# Bus_V3_0.net
KiCad netlist of a schematic drawn in EAGLE
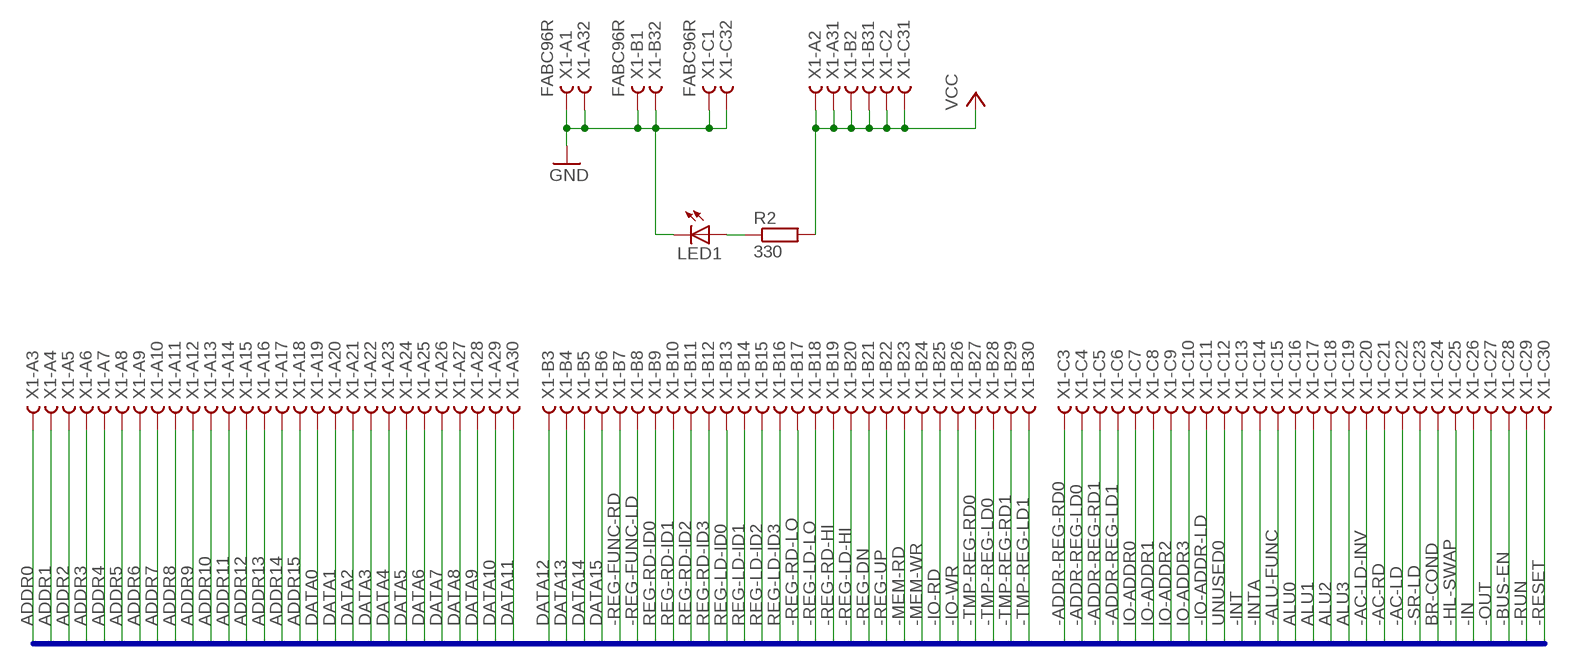
[diagram p0: schematic, sheet 1]

(export (version "E")
  (design (tool "Eeschema 10.0.6"))
  (components
    (comp (ref "LED1")
      (value "LED5MM")
      (footprint "eagle-import:LED5MM")
      (libsource (lib "eagle-import") (part "LED5MM"))
    )
    (comp (ref "R2")
      (value "330")
      (footprint "eagle-import:0207_10")
      (libsource (lib "eagle-import") (part "R0207/10"))
    )
    (comp (ref "X1")
      (value "FABC96R")
      (footprint "eagle-import:FABC96R")
      (libsource (lib "eagle-import") (part "FABC96R"))
    )
  )
  (nets
    (net (code "1") (name "/-AC-LD") (class "Default")
      (node (ref "X1") (pin "C22") (pinfunction "B_C22") (pintype "passive"))
    )
    (net (code "2") (name "/-AC-LD-INV") (class "Default")
      (node (ref "X1") (pin "C20") (pinfunction "B_C20") (pintype "passive"))
    )
    (net (code "3") (name "/-AC-RD") (class "Default")
      (node (ref "X1") (pin "C21") (pinfunction "B_C21") (pintype "passive"))
    )
    (net (code "4") (name "/-ADDR-REG-LD0") (class "Default")
      (node (ref "X1") (pin "C4") (pinfunction "B_C4") (pintype "passive"))
    )
    (net (code "5") (name "/-ADDR-REG-LD1") (class "Default")
      (node (ref "X1") (pin "C6") (pinfunction "B_C6") (pintype "passive"))
    )
    (net (code "6") (name "/-ADDR-REG-RD0") (class "Default")
      (node (ref "X1") (pin "C3") (pinfunction "B_C3") (pintype "passive"))
    )
    (net (code "7") (name "/-ADDR-REG-RD1") (class "Default")
      (node (ref "X1") (pin "C5") (pinfunction "B_C5") (pintype "passive"))
    )
    (net (code "8") (name "/-ALU-FUNC") (class "Default")
      (node (ref "X1") (pin "C15") (pinfunction "B_C15") (pintype "passive"))
    )
    (net (code "9") (name "/-BUS-EN") (class "Default")
      (node (ref "X1") (pin "C28") (pinfunction "B_C28") (pintype "passive"))
    )
    (net (code "10") (name "/-HL-SWAP") (class "Default")
      (node (ref "X1") (pin "C25") (pinfunction "B_C25") (pintype "passive"))
    )
    (net (code "11") (name "/-IN") (class "Default")
      (node (ref "X1") (pin "C26") (pinfunction "B_C26") (pintype "passive"))
    )
    (net (code "12") (name "/-INT") (class "Default")
      (node (ref "X1") (pin "C13") (pinfunction "B_C13") (pintype "passive"))
    )
    (net (code "13") (name "/-INTA") (class "Default")
      (node (ref "X1") (pin "C14") (pinfunction "B_C14") (pintype "passive"))
    )
    (net (code "14") (name "/-IO-ADDR-LD") (class "Default")
      (node (ref "X1") (pin "C11") (pinfunction "B_C11") (pintype "passive"))
    )
    (net (code "15") (name "/-IO-RD") (class "Default")
      (node (ref "X1") (pin "B25") (pinfunction "B_B25") (pintype "passive"))
    )
    (net (code "16") (name "/-IO-WR") (class "Default")
      (node (ref "X1") (pin "B26") (pinfunction "B_B26") (pintype "passive"))
    )
    (net (code "17") (name "/-MEM-RD") (class "Default")
      (node (ref "X1") (pin "B23") (pinfunction "B_B23") (pintype "passive"))
    )
    (net (code "18") (name "/-MEM-WR") (class "Default")
      (node (ref "X1") (pin "B24") (pinfunction "B_B24") (pintype "passive"))
    )
    (net (code "19") (name "/-OUT") (class "Default")
      (node (ref "X1") (pin "C27") (pinfunction "B_C27") (pintype "passive"))
    )
    (net (code "20") (name "/-REG-DN") (class "Default")
      (node (ref "X1") (pin "B21") (pinfunction "B_B21") (pintype "passive"))
    )
    (net (code "21") (name "/-REG-FUNC-LD") (class "Default")
      (node (ref "X1") (pin "B8") (pinfunction "B_B8") (pintype "passive"))
    )
    (net (code "22") (name "/-REG-FUNC-RD") (class "Default")
      (node (ref "X1") (pin "B7") (pinfunction "B_B7") (pintype "passive"))
    )
    (net (code "23") (name "/-REG-LD-HI") (class "Default")
      (node (ref "X1") (pin "B20") (pinfunction "B_B20") (pintype "passive"))
    )
    (net (code "24") (name "/-REG-LD-LO") (class "Default")
      (node (ref "X1") (pin "B18") (pinfunction "B_B18") (pintype "passive"))
    )
    (net (code "25") (name "/-REG-RD-HI") (class "Default")
      (node (ref "X1") (pin "B19") (pinfunction "B_B19") (pintype "passive"))
    )
    (net (code "26") (name "/-REG-RD-LO") (class "Default")
      (node (ref "X1") (pin "B17") (pinfunction "B_B17") (pintype "passive"))
    )
    (net (code "27") (name "/-REG-UP") (class "Default")
      (node (ref "X1") (pin "B22") (pinfunction "B_B22") (pintype "passive"))
    )
    (net (code "28") (name "/-RESET") (class "Default")
      (node (ref "X1") (pin "C30") (pinfunction "B_C30") (pintype "passive"))
    )
    (net (code "29") (name "/-RUN") (class "Default")
      (node (ref "X1") (pin "C29") (pinfunction "B_C29") (pintype "passive"))
    )
    (net (code "30") (name "/-SR-LD") (class "Default")
      (node (ref "X1") (pin "C23") (pinfunction "B_C23") (pintype "passive"))
    )
    (net (code "31") (name "/-TMP-REG-LD0") (class "Default")
      (node (ref "X1") (pin "B28") (pinfunction "B_B28") (pintype "passive"))
    )
    (net (code "32") (name "/-TMP-REG-LD1") (class "Default")
      (node (ref "X1") (pin "B30") (pinfunction "B_B30") (pintype "passive"))
    )
    (net (code "33") (name "/-TMP-REG-RD0") (class "Default")
      (node (ref "X1") (pin "B27") (pinfunction "B_B27") (pintype "passive"))
    )
    (net (code "34") (name "/-TMP-REG-RD1") (class "Default")
      (node (ref "X1") (pin "B29") (pinfunction "B_B29") (pintype "passive"))
    )
    (net (code "35") (name "/ADDR0") (class "Default")
      (node (ref "X1") (pin "A3") (pinfunction "B_A3") (pintype "passive"))
    )
    (net (code "36") (name "/ADDR1") (class "Default")
      (node (ref "X1") (pin "A4") (pinfunction "B_A4") (pintype "passive"))
    )
    (net (code "37") (name "/ADDR2") (class "Default")
      (node (ref "X1") (pin "A5") (pinfunction "B_A5") (pintype "passive"))
    )
    (net (code "38") (name "/ADDR3") (class "Default")
      (node (ref "X1") (pin "A6") (pinfunction "B_A6") (pintype "passive"))
    )
    (net (code "39") (name "/ADDR4") (class "Default")
      (node (ref "X1") (pin "A7") (pinfunction "B_A7") (pintype "passive"))
    )
    (net (code "40") (name "/ADDR5") (class "Default")
      (node (ref "X1") (pin "A8") (pinfunction "B_A8") (pintype "passive"))
    )
    (net (code "41") (name "/ADDR6") (class "Default")
      (node (ref "X1") (pin "A9") (pinfunction "B_A9") (pintype "passive"))
    )
    (net (code "42") (name "/ADDR7") (class "Default")
      (node (ref "X1") (pin "A10") (pinfunction "B_A10") (pintype "passive"))
    )
    (net (code "43") (name "/ADDR8") (class "Default")
      (node (ref "X1") (pin "A11") (pinfunction "B_A11") (pintype "passive"))
    )
    (net (code "44") (name "/ADDR9") (class "Default")
      (node (ref "X1") (pin "A12") (pinfunction "B_A12") (pintype "passive"))
    )
    (net (code "45") (name "/ADDR10") (class "Default")
      (node (ref "X1") (pin "A13") (pinfunction "B_A13") (pintype "passive"))
    )
    (net (code "46") (name "/ADDR11") (class "Default")
      (node (ref "X1") (pin "A14") (pinfunction "B_A14") (pintype "passive"))
    )
    (net (code "47") (name "/ADDR12") (class "Default")
      (node (ref "X1") (pin "A15") (pinfunction "B_A15") (pintype "passive"))
    )
    (net (code "48") (name "/ADDR13") (class "Default")
      (node (ref "X1") (pin "A16") (pinfunction "B_A16") (pintype "passive"))
    )
    (net (code "49") (name "/ADDR14") (class "Default")
      (node (ref "X1") (pin "A17") (pinfunction "B_A17") (pintype "passive"))
    )
    (net (code "50") (name "/ADDR15") (class "Default")
      (node (ref "X1") (pin "A18") (pinfunction "B_A18") (pintype "passive"))
    )
    (net (code "51") (name "/ALU0") (class "Default")
      (node (ref "X1") (pin "C16") (pinfunction "B_C16") (pintype "passive"))
    )
    (net (code "52") (name "/ALU1") (class "Default")
      (node (ref "X1") (pin "C17") (pinfunction "B_C17") (pintype "passive"))
    )
    (net (code "53") (name "/ALU2") (class "Default")
      (node (ref "X1") (pin "C18") (pinfunction "B_C18") (pintype "passive"))
    )
    (net (code "54") (name "/ALU3") (class "Default")
      (node (ref "X1") (pin "C19") (pinfunction "B_C19") (pintype "passive"))
    )
    (net (code "55") (name "/BR-COND") (class "Default")
      (node (ref "X1") (pin "C24") (pinfunction "B_C24") (pintype "passive"))
    )
    (net (code "56") (name "/DATA0") (class "Default")
      (node (ref "X1") (pin "A19") (pinfunction "B_A19") (pintype "passive"))
    )
    (net (code "57") (name "/DATA1") (class "Default")
      (node (ref "X1") (pin "A20") (pinfunction "B_A20") (pintype "passive"))
    )
    (net (code "58") (name "/DATA2") (class "Default")
      (node (ref "X1") (pin "A21") (pinfunction "B_A21") (pintype "passive"))
    )
    (net (code "59") (name "/DATA3") (class "Default")
      (node (ref "X1") (pin "A22") (pinfunction "B_A22") (pintype "passive"))
    )
    (net (code "60") (name "/DATA4") (class "Default")
      (node (ref "X1") (pin "A23") (pinfunction "B_A23") (pintype "passive"))
    )
    (net (code "61") (name "/DATA5") (class "Default")
      (node (ref "X1") (pin "A24") (pinfunction "B_A24") (pintype "passive"))
    )
    (net (code "62") (name "/DATA6") (class "Default")
      (node (ref "X1") (pin "A25") (pinfunction "B_A25") (pintype "passive"))
    )
    (net (code "63") (name "/DATA7") (class "Default")
      (node (ref "X1") (pin "A26") (pinfunction "B_A26") (pintype "passive"))
    )
    (net (code "64") (name "/DATA8") (class "Default")
      (node (ref "X1") (pin "A27") (pinfunction "B_A27") (pintype "passive"))
    )
    (net (code "65") (name "/DATA9") (class "Default")
      (node (ref "X1") (pin "A28") (pinfunction "B_A28") (pintype "passive"))
    )
    (net (code "66") (name "/DATA10") (class "Default")
      (node (ref "X1") (pin "A29") (pinfunction "B_A29") (pintype "passive"))
    )
    (net (code "67") (name "/DATA11") (class "Default")
      (node (ref "X1") (pin "A30") (pinfunction "B_A30") (pintype "passive"))
    )
    (net (code "68") (name "/DATA12") (class "Default")
      (node (ref "X1") (pin "B3") (pinfunction "B_B3") (pintype "passive"))
    )
    (net (code "69") (name "/DATA13") (class "Default")
      (node (ref "X1") (pin "B4") (pinfunction "B_B4") (pintype "passive"))
    )
    (net (code "70") (name "/DATA14") (class "Default")
      (node (ref "X1") (pin "B5") (pinfunction "B_B5") (pintype "passive"))
    )
    (net (code "71") (name "/DATA15") (class "Default")
      (node (ref "X1") (pin "B6") (pinfunction "B_B6") (pintype "passive"))
    )
    (net (code "72") (name "/IO-ADDR0") (class "Default")
      (node (ref "X1") (pin "C7") (pinfunction "B_C7") (pintype "passive"))
    )
    (net (code "73") (name "/IO-ADDR1") (class "Default")
      (node (ref "X1") (pin "C8") (pinfunction "B_C8") (pintype "passive"))
    )
    (net (code "74") (name "/IO-ADDR2") (class "Default")
      (node (ref "X1") (pin "C9") (pinfunction "B_C9") (pintype "passive"))
    )
    (net (code "75") (name "/IO-ADDR3") (class "Default")
      (node (ref "X1") (pin "C10") (pinfunction "B_C10") (pintype "passive"))
    )
    (net (code "76") (name "/REG-LD-ID0") (class "Default")
      (node (ref "X1") (pin "B13") (pinfunction "B_B13") (pintype "passive"))
    )
    (net (code "77") (name "/REG-LD-ID1") (class "Default")
      (node (ref "X1") (pin "B14") (pinfunction "B_B14") (pintype "passive"))
    )
    (net (code "78") (name "/REG-LD-ID2") (class "Default")
      (node (ref "X1") (pin "B15") (pinfunction "B_B15") (pintype "passive"))
    )
    (net (code "79") (name "/REG-LD-ID3") (class "Default")
      (node (ref "X1") (pin "B16") (pinfunction "B_B16") (pintype "passive"))
    )
    (net (code "80") (name "/REG-RD-ID0") (class "Default")
      (node (ref "X1") (pin "B9") (pinfunction "B_B9") (pintype "passive"))
    )
    (net (code "81") (name "/REG-RD-ID1") (class "Default")
      (node (ref "X1") (pin "B10") (pinfunction "B_B10") (pintype "passive"))
    )
    (net (code "82") (name "/REG-RD-ID2") (class "Default")
      (node (ref "X1") (pin "B11") (pinfunction "B_B11") (pintype "passive"))
    )
    (net (code "83") (name "/REG-RD-ID3") (class "Default")
      (node (ref "X1") (pin "B12") (pinfunction "B_B12") (pintype "passive"))
    )
    (net (code "84") (name "/UNUSED0") (class "Default")
      (node (ref "X1") (pin "C12") (pinfunction "B_C12") (pintype "passive"))
    )
    (net (code "85") (name "GND") (class "Default")
      (node (ref "LED1") (pin "K") (pinfunction "C_K") (pintype "passive"))
      (node (ref "X1") (pin "A1") (pinfunction "B_A1") (pintype "passive"))
      (node (ref "X1") (pin "A32") (pinfunction "B_A32") (pintype "passive"))
      (node (ref "X1") (pin "B1") (pinfunction "B_B1") (pintype "passive"))
      (node (ref "X1") (pin "B32") (pinfunction "B_B32") (pintype "passive"))
      (node (ref "X1") (pin "C1") (pinfunction "B_C1") (pintype "passive"))
      (node (ref "X1") (pin "C32") (pinfunction "B_C32") (pintype "passive"))
    )
    (net (code "86") (name "Net-(LED1-PadA)") (class "Default")
      (node (ref "LED1") (pin "A") (pinfunction "A_A") (pintype "passive"))
      (node (ref "R2") (pin "1") (pinfunction "1_1") (pintype "passive"))
    )
    (net (code "87") (name "VCC") (class "Default")
      (node (ref "R2") (pin "2") (pinfunction "2_2") (pintype "passive"))
      (node (ref "X1") (pin "A2") (pinfunction "B_A2") (pintype "passive"))
      (node (ref "X1") (pin "A31") (pinfunction "B_A31") (pintype "passive"))
      (node (ref "X1") (pin "B2") (pinfunction "B_B2") (pintype "passive"))
      (node (ref "X1") (pin "B31") (pinfunction "B_B31") (pintype "passive"))
      (node (ref "X1") (pin "C2") (pinfunction "B_C2") (pintype "passive"))
      (node (ref "X1") (pin "C31") (pinfunction "B_C31") (pintype "passive"))
    )
  )
)
